# SH2_-_MOTOR_CONTROLLER.net
KiCad netlist of a schematic drawn in Altium Designer
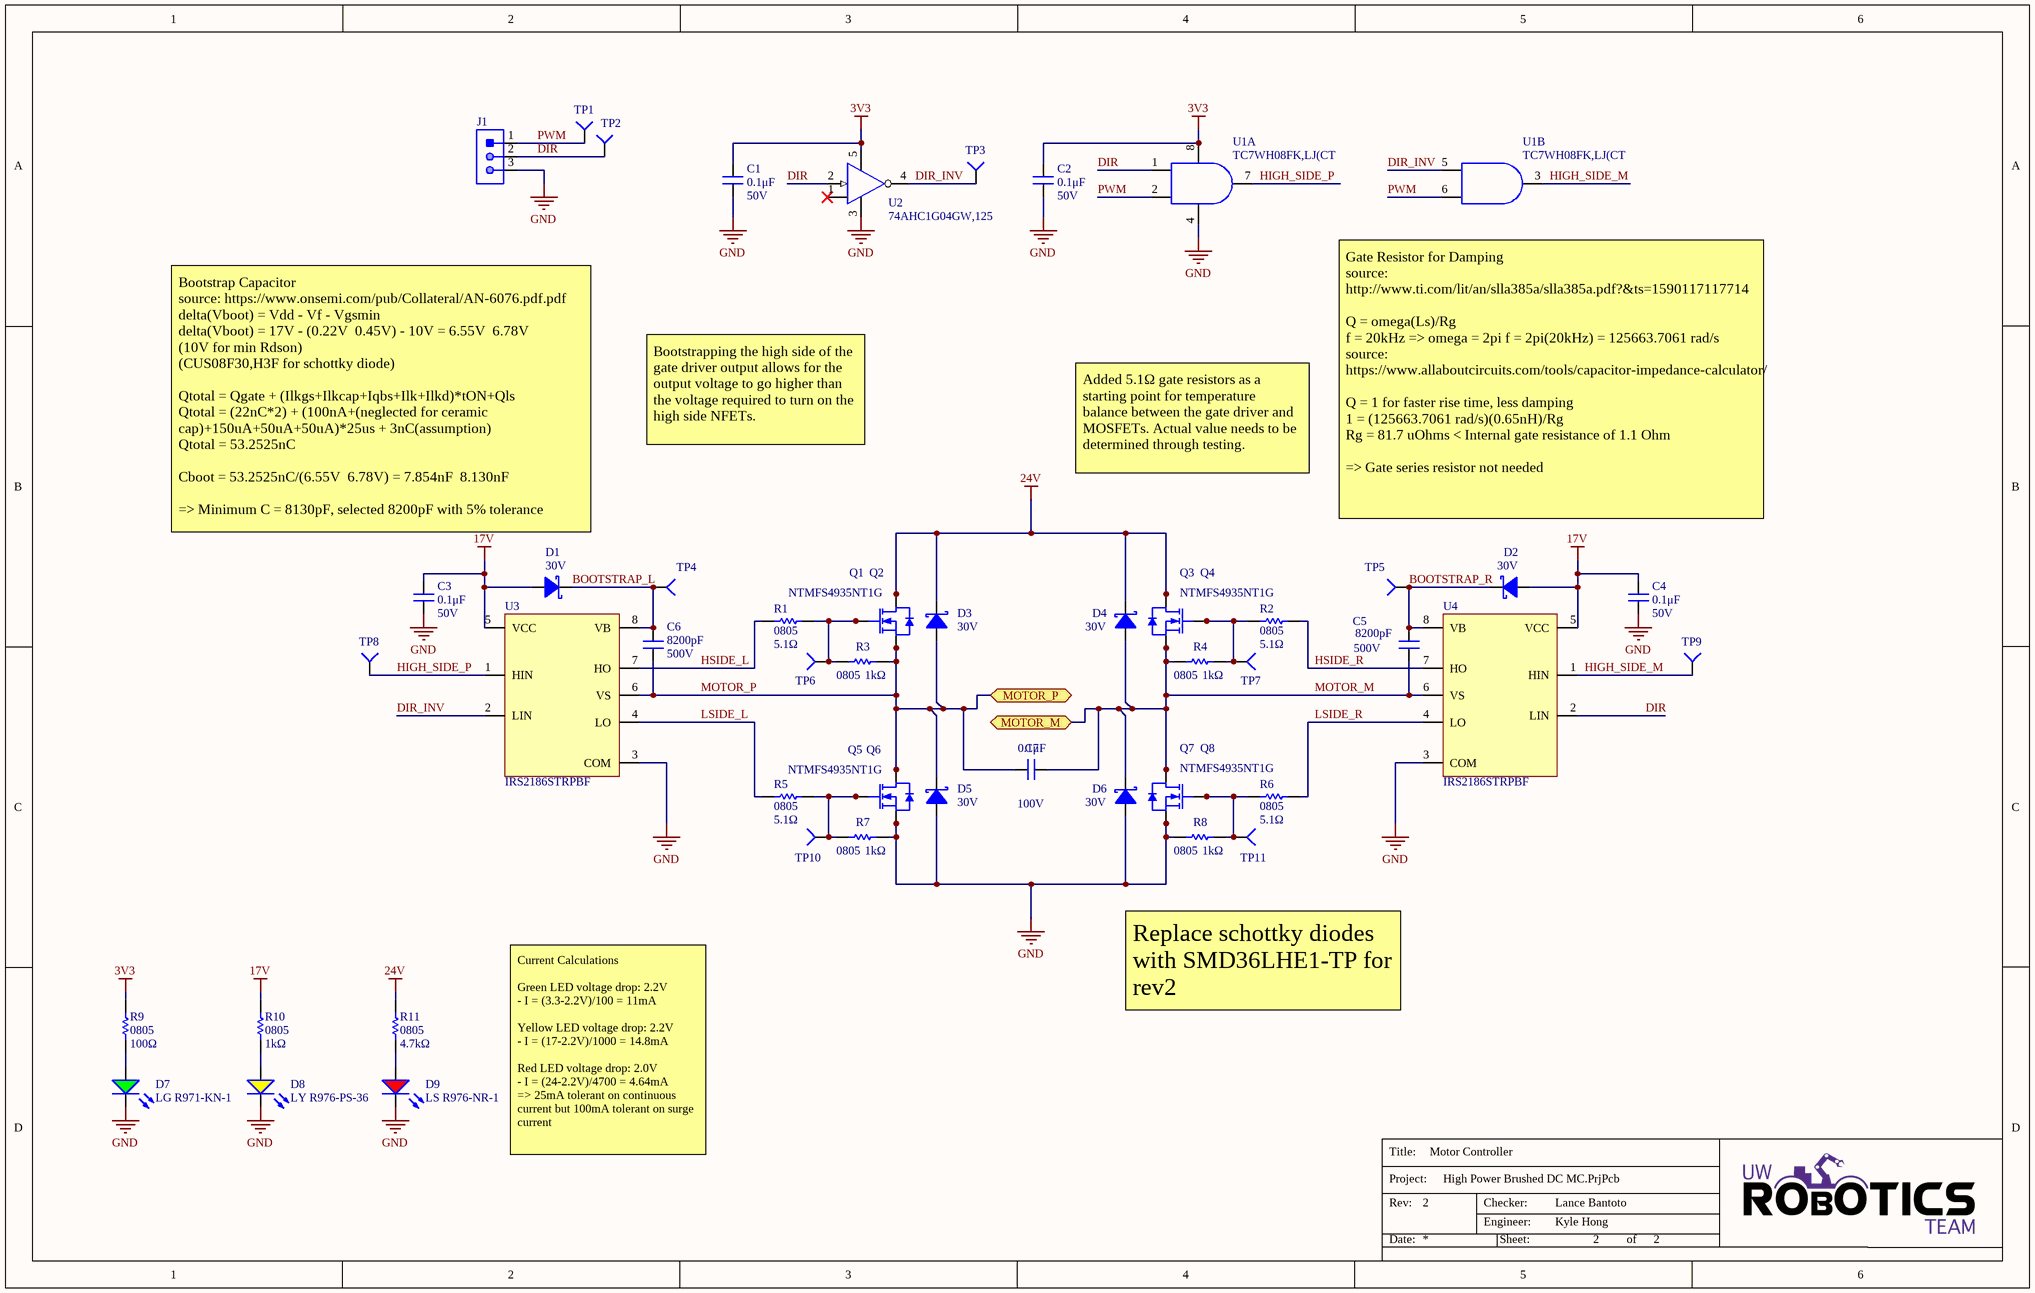
[diagram p0: SH2 - MOTOR CONTROLLER.SchDoc]

(export (version "E")
  (design (tool "Eeschema 10.0.6"))
  (components
    (comp (ref "C1")
      (value "0.1μF")
      (footprint "CAP2012")
      (description "CAP CER 0.1UF 50V X7R 0805")
      (fields (field (name "TOLERANCE") "10%") (field (name "VOLTAGE RATING") "50V"))
      (libsource (lib "UWRT_Schematic_Library_2020") (part "CAP_0.1uF_50V_0805"))
    )
    (comp (ref "C2")
      (value "0.1μF")
      (footprint "CAP2012")
      (description "CAP CER 0.1UF 50V X7R 0805")
      (fields (field (name "TOLERANCE") "10%") (field (name "VOLTAGE RATING") "50V"))
      (libsource (lib "UWRT_Schematic_Library_2020") (part "CAP_0.1uF_50V_0805"))
    )
    (comp (ref "C3")
      (value "0.1μF")
      (footprint "CAP2012")
      (description "CAP CER 0.1UF 50V X7R 0805")
      (fields (field (name "TOLERANCE") "10%") (field (name "VOLTAGE RATING") "50V"))
      (libsource (lib "UWRT_Schematic_Library_2020") (part "CAP_0.1uF_50V_0805"))
    )
    (comp (ref "C4")
      (value "0.1μF")
      (footprint "CAP2012")
      (description "CAP CER 0.1UF 50V X7R 0805")
      (fields (field (name "TOLERANCE") "10%") (field (name "VOLTAGE RATING") "50V"))
      (libsource (lib "UWRT_Schematic_Library_2020") (part "CAP_0.1uF_50V_0805"))
    )
    (comp (ref "C5")
      (value "8200pF")
      (footprint "CAP1206")
      (description "CAP CER 0.0082uF 500Vdc C0G 5% 1206")
      (fields
        (field (name "TOLERANCE") "5%")
        (field (name "VOLTAGE RATING (DC)") "500V")
        (field (name "Comment") "CAP_8200pF_500V_1206")
      )
      (libsource (lib "UWRT_Schematic_Library_2020") (part "CAP_8200pF_500V_1206"))
    )
    (comp (ref "C6")
      (value "8200pF")
      (footprint "CAP1206")
      (description "CAP CER 0.0082uF 500Vdc C0G 5% 1206")
      (fields
        (field (name "TOLERANCE") "5%")
        (field (name "VOLTAGE RATING (DC)") "500V")
        (field (name "Comment") "CAP_8200pF_500V_1206")
      )
      (libsource (lib "UWRT_Schematic_Library_2020") (part "CAP_8200pF_500V_1206"))
    )
    (comp (ref "C7")
      (value "0.1μF")
      (footprint "MKS2D031001A00MSSD")
      (description "CAP FILM 0.1UF 100V RADIAL")
      (fields
        (field (name "TOLERANCE") "20%")
        (field (name "VOLTAGE(DC)") "100V")
        (field (name "Comment") "CAP_0.1uF_100V_FILM")
      )
      (libsource (lib "UWRT_Schematic_Library_2020") (part "CAP_0.1uF_100V_FILM"))
    )
    (comp (ref "D1")
      (value "DIO_SCHOTTKY_30V_800mA")
      (footprint "SOD-323_UNIDIR")
      (description "DIODE SCHOTTKY 30V 800MA USC")
      (fields (field (name "VR (MAX)") "30V"))
      (libsource (lib "UWRT_Schematic_Library_2020") (part "DIO_SCHOTTKY_30V_800mA"))
    )
    (comp (ref "D2")
      (value "DIO_SCHOTTKY_30V_800mA")
      (footprint "SOD-323_UNIDIR")
      (description "DIODE SCHOTTKY 30V 800MA USC")
      (fields (field (name "VR (MAX)") "30V"))
      (libsource (lib "UWRT_Schematic_Library_2020") (part "DIO_SCHOTTKY_30V_800mA"))
    )
    (comp (ref "D3")
      (value "DIO_SCHOTTKY_30V_800mA")
      (footprint "SOD-323_UNIDIR")
      (description "DIODE SCHOTTKY 30V 800MA USC")
      (fields (field (name "VR (MAX)") "30V"))
      (libsource (lib "UWRT_Schematic_Library_2020") (part "DIO_SCHOTTKY_30V_800mA"))
    )
    (comp (ref "D4")
      (value "DIO_SCHOTTKY_30V_800mA")
      (footprint "SOD-323_UNIDIR")
      (description "DIODE SCHOTTKY 30V 800MA USC")
      (fields (field (name "VR (MAX)") "30V"))
      (libsource (lib "UWRT_Schematic_Library_2020") (part "DIO_SCHOTTKY_30V_800mA"))
    )
    (comp (ref "D5")
      (value "DIO_SCHOTTKY_30V_800mA")
      (footprint "SOD-323_UNIDIR")
      (description "DIODE SCHOTTKY 30V 800MA USC")
      (fields (field (name "VR (MAX)") "30V"))
      (libsource (lib "UWRT_Schematic_Library_2020") (part "DIO_SCHOTTKY_30V_800mA"))
    )
    (comp (ref "D6")
      (value "DIO_SCHOTTKY_30V_800mA")
      (footprint "SOD-323_UNIDIR")
      (description "DIODE SCHOTTKY 30V 800MA USC")
      (fields (field (name "VR (MAX)") "30V"))
      (libsource (lib "UWRT_Schematic_Library_2020") (part "DIO_SCHOTTKY_30V_800mA"))
    )
    (comp (ref "D7")
      (value "LG R971-KN-1")
      (footprint "LED_0805_GREEN")
      (description "LED GREEN DIFFUSED 0805 SMD")
      (libsource (lib "UWRT_Schematic_Library_2020") (part "DIO_LED_G"))
    )
    (comp (ref "D8")
      (value "LY R976-PS-36")
      (footprint "LED_0805_YELLOW")
      (description "LED YELLOW DIFFUSED 0805 SMD")
      (libsource (lib "UWRT_Schematic_Library_2020") (part "DIO_LED_Y"))
    )
    (comp (ref "D9")
      (value "LS R976-NR-1")
      (footprint "LED_0805_RED")
      (description "LED RED DIFFUSED 0805 SMD")
      (libsource (lib "UWRT_Schematic_Library_2020") (part "DIO_LED_R"))
    )
    (comp (ref "J1")
      (value "CON_3M_TERM")
      (footprint "1935174")
      (description "TERM BLK 3POS SIDE ENTRY 5MM")
      (fields (field (name "VOLTAGE") "300V"))
      (libsource (lib "UWRT_Schematic_Library_2020") (part "CON_3M_TERM"))
    )
    (comp (ref "Q1")
      (value "NTMFS4935NT1G")
      (footprint "SO8-FL")
      (description "MOSFET N-CH 30V 13A SO8FL")
      (libsource (lib "UWRT_Schematic_Library_2020") (part "NTMFS4935NT1G"))
    )
    (comp (ref "Q2")
      (value "NTMFS4935NT1G")
      (footprint "SO8-FL")
      (description "MOSFET N-CH 30V 13A SO8FL")
      (fields (field (name "MANUFACTURER PART NUMBER 1") "NTMFS4935NT1G"))
      (libsource (lib "UWRT_Schematic_Library_2020") (part "NTMFS4935NT1G"))
    )
    (comp (ref "Q3")
      (value "NTMFS4935NT1G")
      (footprint "SO8-FL")
      (description "MOSFET N-CH 30V 13A SO8FL")
      (fields (field (name "MANUFACTURER PART NUMBER 1") "NTMFS4935NT1G"))
      (libsource (lib "UWRT_Schematic_Library_2020") (part "NTMFS4935NT1G"))
    )
    (comp (ref "Q4")
      (value "NTMFS4935NT1G")
      (footprint "SO8-FL")
      (description "MOSFET N-CH 30V 13A SO8FL")
      (libsource (lib "UWRT_Schematic_Library_2020") (part "NTMFS4935NT1G"))
    )
    (comp (ref "Q5")
      (value "NTMFS4935NT1G")
      (footprint "SO8-FL")
      (description "MOSFET N-CH 30V 13A SO8FL")
      (libsource (lib "UWRT_Schematic_Library_2020") (part "NTMFS4935NT1G"))
    )
    (comp (ref "Q6")
      (value "NTMFS4935NT1G")
      (footprint "SO8-FL")
      (description "MOSFET N-CH 30V 13A SO8FL")
      (fields (field (name "MANUFACTURER PART NUMBER 1") "NTMFS4935NT1G"))
      (libsource (lib "UWRT_Schematic_Library_2020") (part "NTMFS4935NT1G"))
    )
    (comp (ref "Q7")
      (value "NTMFS4935NT1G")
      (footprint "SO8-FL")
      (description "MOSFET N-CH 30V 13A SO8FL")
      (libsource (lib "UWRT_Schematic_Library_2020") (part "NTMFS4935NT1G"))
    )
    (comp (ref "Q8")
      (value "NTMFS4935NT1G")
      (footprint "SO8-FL")
      (description "MOSFET N-CH 30V 13A SO8FL")
      (fields (field (name "MANUFACTURER PART NUMBER 1") "NTMFS4935NT1G"))
      (libsource (lib "UWRT_Schematic_Library_2020") (part "NTMFS4935NT1G"))
    )
    (comp (ref "R1")
      (value "5.1Ω")
      (footprint "RESC2012X60N")
      (description "RES 5.1 OHM 5% 1/8W 0805")
      (fields (field (name "CASE CODE (IMPERIAL)") "0805") (field (name "Comment") "RES_5.1Ω_0805"))
      (libsource (lib "UWRT_Schematic_Library_2020") (part "RES_5.1Ω_0805_5%"))
    )
    (comp (ref "R2")
      (value "5.1Ω")
      (footprint "RESC2012X60N")
      (description "RES 5.1 OHM 5% 1/8W 0805")
      (fields (field (name "CASE CODE (IMPERIAL)") "0805") (field (name "Comment") "RES_5.1Ω_0805"))
      (libsource (lib "UWRT_Schematic_Library_2020") (part "RES_5.1Ω_0805_5%"))
    )
    (comp (ref "R3")
      (value "1kΩ")
      (footprint "RESC2012X60N")
      (description "RES 1K OHM 1% 1/8W 0805")
      (fields (field (name "CASE CODE (IMPERIAL)") "0805") (field (name "TOLERANCE") "1%"))
      (libsource (lib "UWRT_Schematic_Library_2020") (part "RES_1kΩ_0805_1%"))
    )
    (comp (ref "R4")
      (value "1kΩ")
      (footprint "RESC2012X60N")
      (description "RES 1K OHM 1% 1/8W 0805")
      (fields (field (name "CASE CODE (IMPERIAL)") "0805") (field (name "TOLERANCE") "1%"))
      (libsource (lib "UWRT_Schematic_Library_2020") (part "RES_1kΩ_0805_1%"))
    )
    (comp (ref "R5")
      (value "5.1Ω")
      (footprint "RESC2012X60N")
      (description "RES 5.1 OHM 5% 1/8W 0805")
      (fields (field (name "CASE CODE (IMPERIAL)") "0805") (field (name "Comment") "RES_5.1Ω_0805"))
      (libsource (lib "UWRT_Schematic_Library_2020") (part "RES_5.1Ω_0805_5%"))
    )
    (comp (ref "R6")
      (value "5.1Ω")
      (footprint "RESC2012X60N")
      (description "RES 5.1 OHM 5% 1/8W 0805")
      (fields (field (name "CASE CODE (IMPERIAL)") "0805") (field (name "Comment") "RES_5.1Ω_0805"))
      (libsource (lib "UWRT_Schematic_Library_2020") (part "RES_5.1Ω_0805_5%"))
    )
    (comp (ref "R7")
      (value "1kΩ")
      (footprint "RESC2012X60N")
      (description "RES 1K OHM 1% 1/8W 0805")
      (fields (field (name "CASE CODE (IMPERIAL)") "0805") (field (name "TOLERANCE") "1%"))
      (libsource (lib "UWRT_Schematic_Library_2020") (part "RES_1kΩ_0805_1%"))
    )
    (comp (ref "R8")
      (value "1kΩ")
      (footprint "RESC2012X60N")
      (description "RES 1K OHM 1% 1/8W 0805")
      (fields (field (name "CASE CODE (IMPERIAL)") "0805") (field (name "TOLERANCE") "1%"))
      (libsource (lib "UWRT_Schematic_Library_2020") (part "RES_1kΩ_0805_1%"))
    )
    (comp (ref "R9")
      (value "100Ω")
      (footprint "RESC2012X60N")
      (description "RES 100 OHM 1% 1/8W 0805")
      (fields (field (name "CASE CODE (IMPERIAL)") "0805") (field (name "Comment") "RES_100Ω_0805"))
      (libsource (lib "UWRT_Schematic_Library_2020") (part "RES_100Ω_0805_1%"))
    )
    (comp (ref "R10")
      (value "1kΩ")
      (footprint "RESC2012X60N")
      (description "RES 1K OHM 1% 1/8W 0805")
      (fields (field (name "TOLERANCE") "1%") (field (name "CASE CODE (IMPERIAL)") "0805"))
      (libsource (lib "UWRT_Schematic_Library_2020") (part "RES_1kΩ_0805_1%"))
    )
    (comp (ref "R11")
      (value "4.7kΩ")
      (footprint "RESC2012X60N")
      (description "RES 4.7K OHM 5% 1/8W 0805")
      (fields
        (field (name "TOLERANCE") "5%")
        (field (name "CASE CODE (IMPERIAL)") "0805")
        (field (name "Comment") "RES_4.7kΩ_0805")
      )
      (libsource (lib "UWRT_Schematic_Library_2020") (part "RES_4.7kΩ_0805_5%"))
    )
    (comp (ref "TP1")
      (value "TESTPOINT_1MM_CIRCLE")
      (footprint "TESTPOINT_CIRCLE_1MM")
      (description "TESTPOINT 1MM CIRCLE")
      (libsource (lib "UWRT_Schematic_Library_2020") (part "TESTPOINT_1MM_CIRCLE"))
    )
    (comp (ref "TP2")
      (value "TESTPOINT_1MM_CIRCLE")
      (footprint "TESTPOINT_CIRCLE_1MM")
      (description "TESTPOINT 1MM CIRCLE")
      (libsource (lib "UWRT_Schematic_Library_2020") (part "TESTPOINT_1MM_CIRCLE"))
    )
    (comp (ref "TP3")
      (value "TESTPOINT_1MM_CIRCLE")
      (footprint "TESTPOINT_CIRCLE_1MM")
      (description "TESTPOINT 1MM CIRCLE")
      (libsource (lib "UWRT_Schematic_Library_2020") (part "TESTPOINT_1MM_CIRCLE"))
    )
    (comp (ref "TP4")
      (value "TESTPOINT_1MM_CIRCLE")
      (footprint "TESTPOINT_CIRCLE_1MM")
      (description "TESTPOINT 1MM CIRCLE")
      (libsource (lib "UWRT_Schematic_Library_2020") (part "TESTPOINT_1MM_CIRCLE"))
    )
    (comp (ref "TP5")
      (value "TESTPOINT_1MM_CIRCLE")
      (footprint "TESTPOINT_CIRCLE_1MM")
      (description "TESTPOINT 1MM CIRCLE")
      (libsource (lib "UWRT_Schematic_Library_2020") (part "TESTPOINT_1MM_CIRCLE"))
    )
    (comp (ref "TP6")
      (value "TESTPOINT_1MM_CIRCLE")
      (footprint "TESTPOINT_CIRCLE_1MM")
      (description "TESTPOINT 1MM CIRCLE")
      (libsource (lib "UWRT_Schematic_Library_2020") (part "TESTPOINT_1MM_CIRCLE"))
    )
    (comp (ref "TP7")
      (value "TESTPOINT_1MM_CIRCLE")
      (footprint "TESTPOINT_CIRCLE_1MM")
      (description "TESTPOINT 1MM CIRCLE")
      (libsource (lib "UWRT_Schematic_Library_2020") (part "TESTPOINT_1MM_CIRCLE"))
    )
    (comp (ref "TP8")
      (value "TESTPOINT_1MM_CIRCLE")
      (footprint "TESTPOINT_CIRCLE_1MM")
      (description "TESTPOINT 1MM CIRCLE")
      (libsource (lib "UWRT_Schematic_Library_2020") (part "TESTPOINT_1MM_CIRCLE"))
    )
    (comp (ref "TP9")
      (value "TESTPOINT_1MM_CIRCLE")
      (footprint "TESTPOINT_CIRCLE_1MM")
      (description "TESTPOINT 1MM CIRCLE")
      (libsource (lib "UWRT_Schematic_Library_2020") (part "TESTPOINT_1MM_CIRCLE"))
    )
    (comp (ref "TP10")
      (value "TESTPOINT_1MM_CIRCLE")
      (footprint "TESTPOINT_CIRCLE_1MM")
      (description "TESTPOINT 1MM CIRCLE")
      (libsource (lib "UWRT_Schematic_Library_2020") (part "TESTPOINT_1MM_CIRCLE"))
    )
    (comp (ref "TP11")
      (value "TESTPOINT_1MM_CIRCLE")
      (footprint "TESTPOINT_CIRCLE_1MM")
      (description "TESTPOINT 1MM CIRCLE")
      (libsource (lib "UWRT_Schematic_Library_2020") (part "TESTPOINT_1MM_CIRCLE"))
    )
    (comp (ref "U1")
      (value "TC7WH08FK,LJ(CT")
      (footprint "8-VFSOP")
      (description "AND Gate 2-Element 2-IN CMOS Automotive 8-Pin SSOP T/R")
      (fields (field (name "MANUFACTURER PART NUMBER 1") "TC7WH08FK,LJ(CT"))
      (libsource (lib "UWRT_Schematic_Library_2020") (part "TC7WH08FK,LJ(CT"))
    )
    (comp (ref "U2")
      (value "74AHC1G04GW,125")
      (footprint "SOT353")
      (description "IC INVERTER 1CH 1-INP 5TSSOP")
      (fields (field (name "MANUFACTURER PART NUMBER 1") "74AHC1G04GW,125"))
      (libsource (lib "UWRT_Schematic_Library_2020") (part "74AHC1G04GW,125"))
    )
    (comp (ref "U3")
      (value "IRS2186STRPBF")
      (footprint "8-SOIC_M")
      (description "IC DRIVER HI/LO SIDE 600V 8-SOIC")
      (fields (field (name "MANUFACTURER PART NUMBER 1") "IRS2186STRPBF"))
      (libsource (lib "") (part "IRS2186STRPBF_1"))
    )
    (comp (ref "U4")
      (value "IRS2186STRPBF")
      (footprint "8-SOIC_M")
      (description "IC DRIVER HI/LO SIDE 600V 8-SOIC")
      (fields (field (name "MANUFACTURER PART NUMBER 1") "IRS2186STRPBF"))
      (libsource (lib "UWRT_Schematic_Library_2020") (part "IRS2186STRPBF"))
    )
  )
  (nets
    (net (code "1") (name "/BOOTSTRAP_L") (class "Default")
      (node (ref "C6") (pin "2") (pinfunction "2_2") (pintype "passive"))
      (node (ref "D1") (pin "2") (pinfunction "Cathode_2") (pintype "passive"))
      (node (ref "TP4") (pin "1") (pinfunction "=value_1") (pintype "passive"))
      (node (ref "U3") (pin "8") (pinfunction "VB_8") (pintype "passive"))
    )
    (net (code "2") (name "/BOOTSTRAP_R") (class "Default")
      (node (ref "C5") (pin "2") (pinfunction "2_2") (pintype "passive"))
      (node (ref "D2") (pin "2") (pinfunction "Cathode_2") (pintype "passive"))
      (node (ref "TP5") (pin "1") (pinfunction "=value_1") (pintype "passive"))
      (node (ref "U4") (pin "8") (pinfunction "VB_8") (pintype "passive"))
    )
    (net (code "3") (name "/DIR") (class "Default")
      (node (ref "J1") (pin "2") (pinfunction "2_2") (pintype "passive"))
      (node (ref "TP2") (pin "1") (pinfunction "=value_1") (pintype "passive"))
      (node (ref "U1") (pin "1") (pinfunction "A1_1") (pintype "passive"))
      (node (ref "U2") (pin "2") (pinfunction "A_2") (pintype "input"))
      (node (ref "U4") (pin "2") (pinfunction "LIN_2") (pintype "passive"))
    )
    (net (code "4") (name "/DIR_INV") (class "Default")
      (node (ref "TP3") (pin "1") (pinfunction "=value_1") (pintype "passive"))
      (node (ref "U1") (pin "5") (pinfunction "A2_5") (pintype "passive"))
      (node (ref "U2") (pin "4") (pinfunction "Y_4") (pintype "passive"))
      (node (ref "U3") (pin "2") (pinfunction "LIN_2") (pintype "passive"))
    )
    (net (code "5") (name "/HIGH_SIDE_M") (class "Default")
      (node (ref "TP9") (pin "1") (pinfunction "=value_1") (pintype "passive"))
      (node (ref "U1") (pin "3") (pinfunction "Y2_3") (pintype "passive"))
      (node (ref "U4") (pin "1") (pinfunction "HIN_1") (pintype "passive"))
    )
    (net (code "6") (name "/HIGH_SIDE_P") (class "Default")
      (node (ref "TP8") (pin "1") (pinfunction "=value_1") (pintype "passive"))
      (node (ref "U1") (pin "7") (pinfunction "Y1_7") (pintype "passive"))
      (node (ref "U3") (pin "1") (pinfunction "HIN_1") (pintype "passive"))
    )
    (net (code "7") (name "/HSIDE_L") (class "Default")
      (node (ref "R1") (pin "1") (pinfunction "1_1") (pintype "passive"))
      (node (ref "U3") (pin "7") (pinfunction "HO_7") (pintype "passive"))
    )
    (net (code "8") (name "/HSIDE_R") (class "Default")
      (node (ref "R2") (pin "2") (pinfunction "2_2") (pintype "passive"))
      (node (ref "U4") (pin "7") (pinfunction "HO_7") (pintype "passive"))
    )
    (net (code "9") (name "/LSIDE_L") (class "Default")
      (node (ref "R5") (pin "1") (pinfunction "1_1") (pintype "passive"))
      (node (ref "U3") (pin "4") (pinfunction "LO_4") (pintype "passive"))
    )
    (net (code "10") (name "/LSIDE_R") (class "Default")
      (node (ref "R6") (pin "2") (pinfunction "2_2") (pintype "passive"))
      (node (ref "U4") (pin "4") (pinfunction "LO_4") (pintype "passive"))
    )
    (net (code "11") (name "/MOTOR_M") (class "Default")
      (node (ref "C5") (pin "1") (pinfunction "1_1") (pintype "passive"))
      (node (ref "C7") (pin "2") (pinfunction "2_2") (pintype "passive"))
      (node (ref "D4") (pin "1") (pinfunction "Anode_1") (pintype "passive"))
      (node (ref "D6") (pin "2") (pinfunction "Cathode_2") (pintype "passive"))
      (node (ref "Q3") (pin "1") (pinfunction "Source_1") (pintype "passive"))
      (node (ref "Q4") (pin "1") (pinfunction "Source_1") (pintype "passive"))
      (node (ref "Q7") (pin "3") (pinfunction "Drain_3") (pintype "passive"))
      (node (ref "Q8") (pin "3") (pinfunction "Drain_3") (pintype "passive"))
      (node (ref "R4") (pin "1") (pinfunction "1_1") (pintype "passive"))
      (node (ref "U4") (pin "6") (pinfunction "VS_6") (pintype "passive"))
    )
    (net (code "12") (name "/MOTOR_P") (class "Default")
      (node (ref "C6") (pin "1") (pinfunction "1_1") (pintype "passive"))
      (node (ref "C7") (pin "1") (pinfunction "1_1") (pintype "passive"))
      (node (ref "D3") (pin "1") (pinfunction "Anode_1") (pintype "passive"))
      (node (ref "D5") (pin "2") (pinfunction "Cathode_2") (pintype "passive"))
      (node (ref "Q1") (pin "1") (pinfunction "Source_1") (pintype "passive"))
      (node (ref "Q2") (pin "1") (pinfunction "Source_1") (pintype "passive"))
      (node (ref "Q5") (pin "3") (pinfunction "Drain_3") (pintype "passive"))
      (node (ref "Q6") (pin "3") (pinfunction "Drain_3") (pintype "passive"))
      (node (ref "R3") (pin "2") (pinfunction "2_2") (pintype "passive"))
      (node (ref "U3") (pin "6") (pinfunction "VS_6") (pintype "passive"))
    )
    (net (code "13") (name "/PWM") (class "Default")
      (node (ref "J1") (pin "1") (pinfunction "1_1") (pintype "passive"))
      (node (ref "TP1") (pin "1") (pinfunction "=value_1") (pintype "passive"))
      (node (ref "U1") (pin "2") (pinfunction "B1_2") (pintype "passive"))
      (node (ref "U1") (pin "6") (pinfunction "B2_6") (pintype "passive"))
    )
    (net (code "14") (name "3V3") (class "Default")
      (node (ref "C1") (pin "2") (pinfunction "2_2") (pintype "passive"))
      (node (ref "C2") (pin "2") (pinfunction "2_2") (pintype "passive"))
      (node (ref "R9") (pin "2") (pinfunction "2_2") (pintype "passive"))
      (node (ref "U1") (pin "8") (pinfunction "Vcc_8") (pintype "passive"))
      (node (ref "U2") (pin "5") (pinfunction "Vcc_5") (pintype "passive"))
    )
    (net (code "15") (name "17V") (class "Default")
      (node (ref "C3") (pin "2") (pinfunction "2_2") (pintype "passive"))
      (node (ref "C4") (pin "2") (pinfunction "2_2") (pintype "passive"))
      (node (ref "D1") (pin "1") (pinfunction "Anode_1") (pintype "passive"))
      (node (ref "D2") (pin "1") (pinfunction "Anode_1") (pintype "passive"))
      (node (ref "R10") (pin "2") (pinfunction "2_2") (pintype "passive"))
      (node (ref "U3") (pin "5") (pinfunction "VCC_5") (pintype "passive"))
      (node (ref "U4") (pin "5") (pinfunction "VCC_5") (pintype "passive"))
    )
    (net (code "16") (name "24V") (class "Default")
      (node (ref "D3") (pin "2") (pinfunction "Cathode_2") (pintype "passive"))
      (node (ref "D4") (pin "2") (pinfunction "Cathode_2") (pintype "passive"))
      (node (ref "Q1") (pin "3") (pinfunction "Drain_3") (pintype "passive"))
      (node (ref "Q2") (pin "3") (pinfunction "Drain_3") (pintype "passive"))
      (node (ref "Q3") (pin "3") (pinfunction "Drain_3") (pintype "passive"))
      (node (ref "Q4") (pin "3") (pinfunction "Drain_3") (pintype "passive"))
      (node (ref "R11") (pin "2") (pinfunction "2_2") (pintype "passive"))
    )
    (net (code "17") (name "GND") (class "Default")
      (node (ref "C1") (pin "1") (pinfunction "1_1") (pintype "passive"))
      (node (ref "C2") (pin "1") (pinfunction "1_1") (pintype "passive"))
      (node (ref "C3") (pin "1") (pinfunction "1_1") (pintype "passive"))
      (node (ref "C4") (pin "1") (pinfunction "1_1") (pintype "passive"))
      (node (ref "D5") (pin "1") (pinfunction "Anode_1") (pintype "passive"))
      (node (ref "D6") (pin "1") (pinfunction "Anode_1") (pintype "passive"))
      (node (ref "D7") (pin "2") (pinfunction "K_2") (pintype "passive"))
      (node (ref "D8") (pin "2") (pinfunction "K_2") (pintype "passive"))
      (node (ref "D9") (pin "2") (pinfunction "K_2") (pintype "passive"))
      (node (ref "J1") (pin "3") (pinfunction "3_3") (pintype "passive"))
      (node (ref "Q5") (pin "1") (pinfunction "Source_1") (pintype "passive"))
      (node (ref "Q6") (pin "1") (pinfunction "Source_1") (pintype "passive"))
      (node (ref "Q7") (pin "1") (pinfunction "Source_1") (pintype "passive"))
      (node (ref "Q8") (pin "1") (pinfunction "Source_1") (pintype "passive"))
      (node (ref "R7") (pin "2") (pinfunction "2_2") (pintype "passive"))
      (node (ref "R8") (pin "1") (pinfunction "1_1") (pintype "passive"))
      (node (ref "U1") (pin "4") (pinfunction "GND_4") (pintype "passive"))
      (node (ref "U2") (pin "3") (pinfunction "GND_3") (pintype "passive"))
      (node (ref "U3") (pin "3") (pinfunction "COM_3") (pintype "passive"))
      (node (ref "U4") (pin "3") (pinfunction "COM_3") (pintype "passive"))
    )
    (net (code "18") (name "Net-(D7-A)") (class "Default")
      (node (ref "D7") (pin "1") (pinfunction "A_1") (pintype "passive"))
      (node (ref "R9") (pin "1") (pinfunction "1_1") (pintype "passive"))
    )
    (net (code "19") (name "Net-(D8-A)") (class "Default")
      (node (ref "D8") (pin "1") (pinfunction "A_1") (pintype "passive"))
      (node (ref "R10") (pin "1") (pinfunction "1_1") (pintype "passive"))
    )
    (net (code "20") (name "Net-(D9-A)") (class "Default")
      (node (ref "D9") (pin "1") (pinfunction "A_1") (pintype "passive"))
      (node (ref "R11") (pin "1") (pinfunction "1_1") (pintype "passive"))
    )
    (net (code "21") (name "Net-(Q1-Gate)") (class "Default")
      (node (ref "Q1") (pin "2") (pinfunction "Gate_2") (pintype "passive"))
      (node (ref "Q2") (pin "2") (pinfunction "Gate_2") (pintype "passive"))
      (node (ref "R1") (pin "2") (pinfunction "2_2") (pintype "passive"))
      (node (ref "R3") (pin "1") (pinfunction "1_1") (pintype "passive"))
      (node (ref "TP6") (pin "1") (pinfunction "=value_1") (pintype "passive"))
    )
    (net (code "22") (name "Net-(Q3-Gate)") (class "Default")
      (node (ref "Q3") (pin "2") (pinfunction "Gate_2") (pintype "passive"))
      (node (ref "Q4") (pin "2") (pinfunction "Gate_2") (pintype "passive"))
      (node (ref "R2") (pin "1") (pinfunction "1_1") (pintype "passive"))
      (node (ref "R4") (pin "2") (pinfunction "2_2") (pintype "passive"))
      (node (ref "TP7") (pin "1") (pinfunction "=value_1") (pintype "passive"))
    )
    (net (code "23") (name "Net-(Q5-Gate)") (class "Default")
      (node (ref "Q5") (pin "2") (pinfunction "Gate_2") (pintype "passive"))
      (node (ref "Q6") (pin "2") (pinfunction "Gate_2") (pintype "passive"))
      (node (ref "R5") (pin "2") (pinfunction "2_2") (pintype "passive"))
      (node (ref "R7") (pin "1") (pinfunction "1_1") (pintype "passive"))
      (node (ref "TP10") (pin "1") (pinfunction "=value_1") (pintype "passive"))
    )
    (net (code "24") (name "Net-(Q7-Gate)") (class "Default")
      (node (ref "Q7") (pin "2") (pinfunction "Gate_2") (pintype "passive"))
      (node (ref "Q8") (pin "2") (pinfunction "Gate_2") (pintype "passive"))
      (node (ref "R6") (pin "1") (pinfunction "1_1") (pintype "passive"))
      (node (ref "R8") (pin "2") (pinfunction "2_2") (pintype "passive"))
      (node (ref "TP11") (pin "1") (pinfunction "=value_1") (pintype "passive"))
    )
    (net (code "25") (name "unconnected-(U2-NC-Pad1)") (class "Default")
      (node (ref "U2") (pin "1") (pinfunction "NC_1") (pintype "tri_state+no_connect"))
    )
  )
)
